# Main_Board.net
KiCad netlist of a schematic drawn in EAGLE
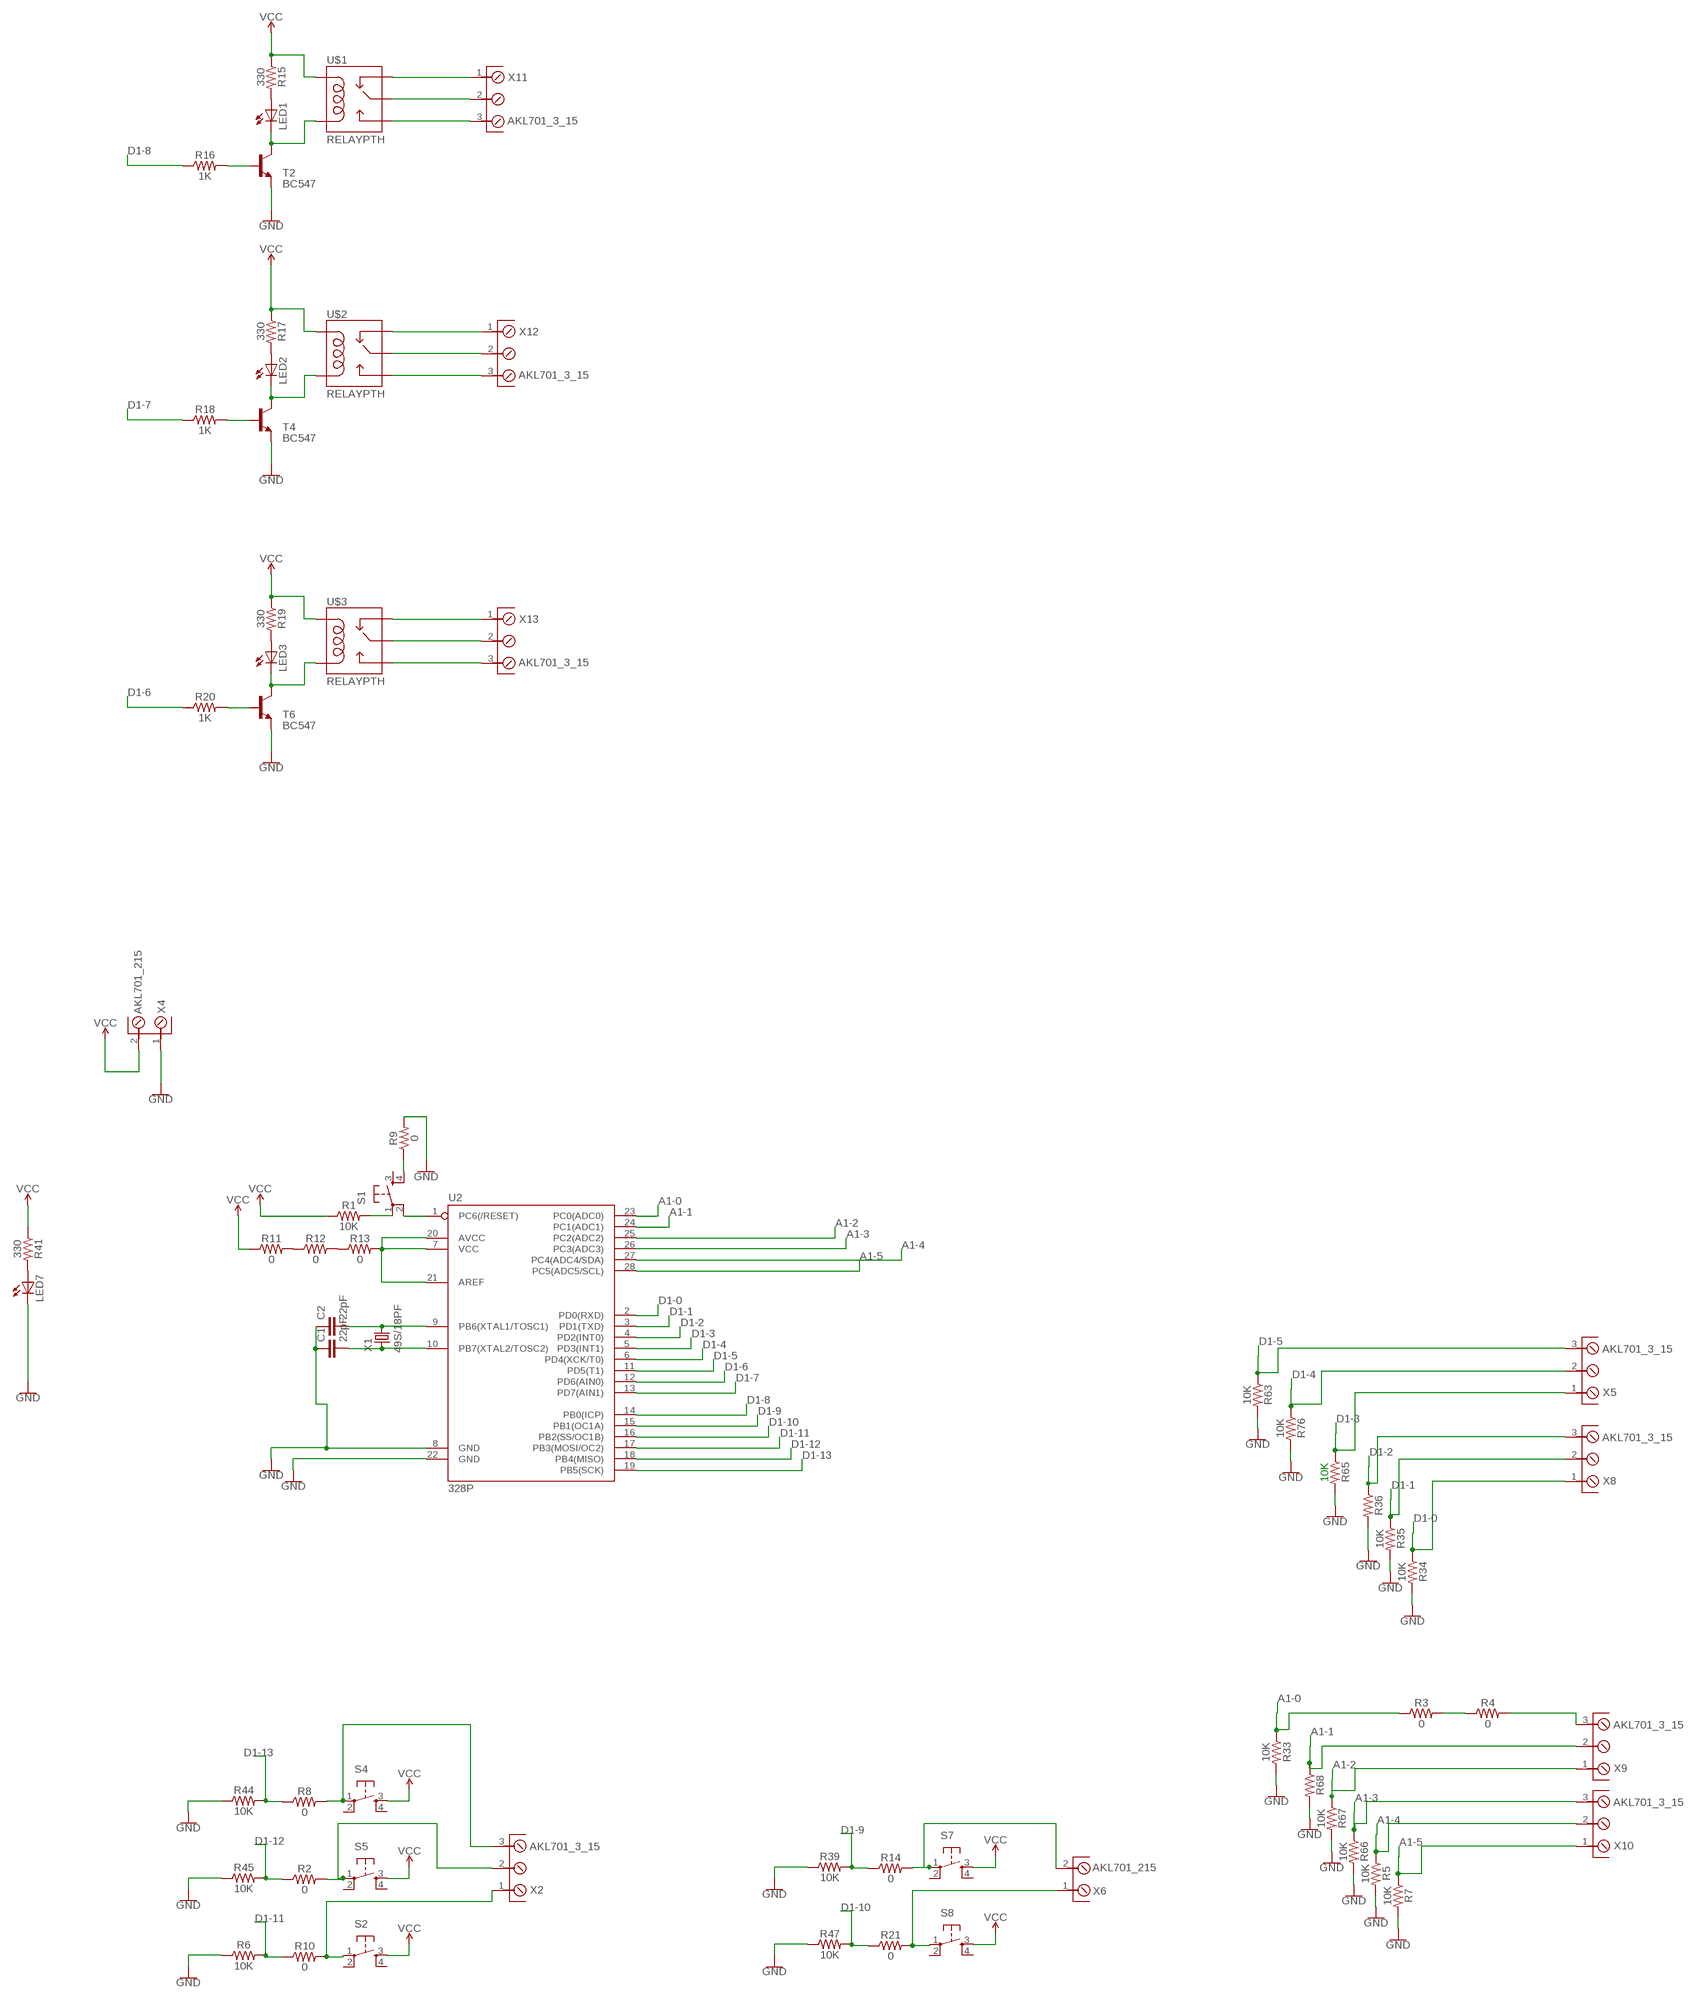
[diagram p0: schematic, sheet 1]

(export (version "E")
  (design (tool "Eeschema 10.0.6"))
  (components
    (comp (ref "C1")
      (value "22pF")
      (footprint "eagle-import:CAP-PTH-2.54")
      (libsource (lib "eagle-import") (part "22PF-PTH-2.54MM-200V-5%"))
    )
    (comp (ref "C2")
      (value "22pF")
      (footprint "eagle-import:CAP-PTH-2.54")
      (libsource (lib "eagle-import") (part "22PF-PTH-2.54MM-200V-5%"))
    )
    (comp (ref "LED1")
      (value "LED5MM")
      (footprint "eagle-import:LED5MM")
      (libsource (lib "eagle-import") (part "LED5MM"))
    )
    (comp (ref "LED2")
      (value "LED5MM")
      (footprint "eagle-import:LED5MM")
      (libsource (lib "eagle-import") (part "LED5MM"))
    )
    (comp (ref "LED3")
      (value "LED5MM")
      (footprint "eagle-import:LED5MM")
      (libsource (lib "eagle-import") (part "LED5MM"))
    )
    (comp (ref "LED7")
      (value "LED5MM")
      (footprint "eagle-import:LED5MM")
      (libsource (lib "eagle-import") (part "LED5MM"))
    )
    (comp (ref "R1")
      (value "10K")
      (footprint "eagle-import:AXIAL-0.3")
      (libsource (lib "eagle-import") (part "10MOHM-HORIZ-1/4W-5%"))
    )
    (comp (ref "R2")
      (value "0")
      (footprint "eagle-import:AXIAL-0.3")
      (libsource (lib "eagle-import") (part "10MOHM-HORIZ-1/4W-5%"))
    )
    (comp (ref "R3")
      (value "0")
      (footprint "eagle-import:AXIAL-0.3")
      (libsource (lib "eagle-import") (part "10MOHM-HORIZ-1/4W-5%"))
    )
    (comp (ref "R4")
      (value "0")
      (footprint "eagle-import:AXIAL-0.3")
      (libsource (lib "eagle-import") (part "10MOHM-HORIZ-1/4W-5%"))
    )
    (comp (ref "R5")
      (value "10K")
      (footprint "eagle-import:AXIAL-0.3")
      (libsource (lib "eagle-import") (part "10MOHM-HORIZ-1/4W-5%"))
    )
    (comp (ref "R6")
      (value "10K")
      (footprint "eagle-import:AXIAL-0.3")
      (libsource (lib "eagle-import") (part "10MOHM-HORIZ-1/4W-5%"))
    )
    (comp (ref "R7")
      (value "10K")
      (footprint "eagle-import:AXIAL-0.3")
      (libsource (lib "eagle-import") (part "10MOHM-HORIZ-1/4W-5%"))
    )
    (comp (ref "R8")
      (value "0")
      (footprint "eagle-import:AXIAL-0.3")
      (libsource (lib "eagle-import") (part "10MOHM-HORIZ-1/4W-5%"))
    )
    (comp (ref "R9")
      (value "0")
      (footprint "eagle-import:AXIAL-0.3")
      (libsource (lib "eagle-import") (part "10MOHM-HORIZ-1/4W-5%"))
    )
    (comp (ref "R10")
      (value "0")
      (footprint "eagle-import:AXIAL-0.3")
      (libsource (lib "eagle-import") (part "10MOHM-HORIZ-1/4W-5%"))
    )
    (comp (ref "R11")
      (value "0")
      (footprint "eagle-import:AXIAL-0.3")
      (libsource (lib "eagle-import") (part "10MOHM-HORIZ-1/4W-5%"))
    )
    (comp (ref "R12")
      (value "0")
      (footprint "eagle-import:AXIAL-0.3")
      (libsource (lib "eagle-import") (part "10MOHM-HORIZ-1/4W-5%"))
    )
    (comp (ref "R13")
      (value "0")
      (footprint "eagle-import:AXIAL-0.3")
      (libsource (lib "eagle-import") (part "10MOHM-HORIZ-1/4W-5%"))
    )
    (comp (ref "R14")
      (value "0")
      (footprint "eagle-import:AXIAL-0.3")
      (libsource (lib "eagle-import") (part "10MOHM-HORIZ-1/4W-5%"))
    )
    (comp (ref "R15")
      (value "330")
      (footprint "eagle-import:AXIAL-0.3")
      (libsource (lib "eagle-import") (part "10MOHM-HORIZ-1/4W-5%"))
    )
    (comp (ref "R16")
      (value "1K")
      (footprint "eagle-import:AXIAL-0.3")
      (libsource (lib "eagle-import") (part "10MOHM-HORIZ-1/4W-5%"))
    )
    (comp (ref "R17")
      (value "330")
      (footprint "eagle-import:AXIAL-0.3")
      (libsource (lib "eagle-import") (part "10MOHM-HORIZ-1/4W-5%"))
    )
    (comp (ref "R18")
      (value "1K")
      (footprint "eagle-import:AXIAL-0.3")
      (libsource (lib "eagle-import") (part "10MOHM-HORIZ-1/4W-5%"))
    )
    (comp (ref "R19")
      (value "330")
      (footprint "eagle-import:AXIAL-0.3")
      (libsource (lib "eagle-import") (part "10MOHM-HORIZ-1/4W-5%"))
    )
    (comp (ref "R20")
      (value "1K")
      (footprint "eagle-import:AXIAL-0.3")
      (libsource (lib "eagle-import") (part "10MOHM-HORIZ-1/4W-5%"))
    )
    (comp (ref "R21")
      (value "0")
      (footprint "eagle-import:AXIAL-0.3")
      (libsource (lib "eagle-import") (part "10MOHM-HORIZ-1/4W-5%"))
    )
    (comp (ref "R33")
      (value "10K")
      (footprint "eagle-import:AXIAL-0.3")
      (libsource (lib "eagle-import") (part "10MOHM-HORIZ-1/4W-5%"))
    )
    (comp (ref "R34")
      (value "10K")
      (footprint "eagle-import:AXIAL-0.3")
      (libsource (lib "eagle-import") (part "10MOHM-HORIZ-1/4W-5%"))
    )
    (comp (ref "R35")
      (value "10K")
      (footprint "eagle-import:AXIAL-0.3")
      (libsource (lib "eagle-import") (part "10MOHM-HORIZ-1/4W-5%"))
    )
    (comp (ref "R36")
      (value "10K")
      (footprint "eagle-import:AXIAL-0.3")
      (libsource (lib "eagle-import") (part "10MOHM-HORIZ-1/4W-5%"))
    )
    (comp (ref "R39")
      (value "10K")
      (footprint "eagle-import:AXIAL-0.3")
      (libsource (lib "eagle-import") (part "10MOHM-HORIZ-1/4W-5%"))
    )
    (comp (ref "R41")
      (value "330")
      (footprint "eagle-import:AXIAL-0.3")
      (libsource (lib "eagle-import") (part "10MOHM-HORIZ-1/4W-5%"))
    )
    (comp (ref "R44")
      (value "10K")
      (footprint "eagle-import:AXIAL-0.3")
      (libsource (lib "eagle-import") (part "10MOHM-HORIZ-1/4W-5%"))
    )
    (comp (ref "R45")
      (value "10K")
      (footprint "eagle-import:AXIAL-0.3")
      (libsource (lib "eagle-import") (part "10MOHM-HORIZ-1/4W-5%"))
    )
    (comp (ref "R47")
      (value "10K")
      (footprint "eagle-import:AXIAL-0.3")
      (libsource (lib "eagle-import") (part "10MOHM-HORIZ-1/4W-5%"))
    )
    (comp (ref "R63")
      (value "10K")
      (footprint "eagle-import:AXIAL-0.3")
      (libsource (lib "eagle-import") (part "10MOHM-HORIZ-1/4W-5%"))
    )
    (comp (ref "R65")
      (value "10K")
      (footprint "eagle-import:AXIAL-0.3")
      (libsource (lib "eagle-import") (part "10MOHM-HORIZ-1/4W-5%"))
    )
    (comp (ref "R66")
      (value "10K")
      (footprint "eagle-import:AXIAL-0.3")
      (libsource (lib "eagle-import") (part "10MOHM-HORIZ-1/4W-5%"))
    )
    (comp (ref "R67")
      (value "10K")
      (footprint "eagle-import:AXIAL-0.3")
      (libsource (lib "eagle-import") (part "10MOHM-HORIZ-1/4W-5%"))
    )
    (comp (ref "R68")
      (value "10K")
      (footprint "eagle-import:AXIAL-0.3")
      (libsource (lib "eagle-import") (part "10MOHM-HORIZ-1/4W-5%"))
    )
    (comp (ref "R76")
      (value "10K")
      (footprint "eagle-import:AXIAL-0.3")
      (libsource (lib "eagle-import") (part "10MOHM-HORIZ-1/4W-5%"))
    )
    (comp (ref "S1")
      (value "TAC_SWITCHPTH")
      (footprint "eagle-import:TACTILE-PTH")
      (libsource (lib "eagle-import") (part "TAC_SWITCHPTH"))
    )
    (comp (ref "S2")
      (value "TAC_SWITCHPTH")
      (footprint "eagle-import:TACTILE-PTH")
      (libsource (lib "eagle-import") (part "TAC_SWITCHPTH"))
    )
    (comp (ref "S4")
      (value "TAC_SWITCHPTH")
      (footprint "eagle-import:TACTILE-PTH")
      (libsource (lib "eagle-import") (part "TAC_SWITCHPTH"))
    )
    (comp (ref "S5")
      (value "TAC_SWITCHPTH")
      (footprint "eagle-import:TACTILE-PTH")
      (libsource (lib "eagle-import") (part "TAC_SWITCHPTH"))
    )
    (comp (ref "S7")
      (value "TAC_SWITCHPTH")
      (footprint "eagle-import:TACTILE-PTH")
      (libsource (lib "eagle-import") (part "TAC_SWITCHPTH"))
    )
    (comp (ref "S8")
      (value "TAC_SWITCHPTH")
      (footprint "eagle-import:TACTILE-PTH")
      (libsource (lib "eagle-import") (part "TAC_SWITCHPTH"))
    )
    (comp (ref "T2")
      (value "BC547")
      (footprint "eagle-import:TO92")
      (libsource (lib "eagle-import") (part "BC547"))
    )
    (comp (ref "T4")
      (value "BC547")
      (footprint "eagle-import:TO92")
      (libsource (lib "eagle-import") (part "BC547"))
    )
    (comp (ref "T6")
      (value "BC547")
      (footprint "eagle-import:TO92")
      (libsource (lib "eagle-import") (part "BC547"))
    )
    (comp (ref "U$1")
      (value "RELAYPTH")
      (footprint "eagle-import:SRD-05VDC-SL-C")
      (libsource (lib "eagle-import") (part "RELAYPTH"))
    )
    (comp (ref "U$2")
      (value "RELAYPTH")
      (footprint "eagle-import:SRD-05VDC-SL-C")
      (libsource (lib "eagle-import") (part "RELAYPTH"))
    )
    (comp (ref "U$3")
      (value "RELAYPTH")
      (footprint "eagle-import:SRD-05VDC-SL-C")
      (libsource (lib "eagle-import") (part "RELAYPTH"))
    )
    (comp (ref "U2")
      (value "328P")
      (footprint "eagle-import:DIP28")
      (libsource (lib "eagle-import") (part "ATMEGA328P_PDIP"))
    )
    (comp (ref "X1")
      (value "49S/18PF")
      (footprint "eagle-import:XTAL_HC49")
      (fields (field (name "MANUFACTURER") "Xinhunjing ") (field (name "CREATED_BY") "PCBLayout.com"))
      (libsource (lib "eagle-import") (part "49S/18PF"))
    )
    (comp (ref "X2")
      (value "AKL701_3_15")
      (footprint "eagle-import:AKL701_3_15")
      (libsource (lib "eagle-import") (part "AKL701_3_15"))
    )
    (comp (ref "X4")
      (value "AKL701_215")
      (footprint "eagle-import:AKL701_2_15")
      (libsource (lib "eagle-import") (part "AKL701_215"))
    )
    (comp (ref "X5")
      (value "AKL701_3_15")
      (footprint "eagle-import:AKL701_3_15")
      (libsource (lib "eagle-import") (part "AKL701_3_15"))
    )
    (comp (ref "X6")
      (value "AKL701_215")
      (footprint "eagle-import:AKL701_2_15")
      (libsource (lib "eagle-import") (part "AKL701_215"))
    )
    (comp (ref "X8")
      (value "AKL701_3_15")
      (footprint "eagle-import:AKL701_3_15")
      (libsource (lib "eagle-import") (part "AKL701_3_15"))
    )
    (comp (ref "X9")
      (value "AKL701_3_15")
      (footprint "eagle-import:AKL701_3_15")
      (libsource (lib "eagle-import") (part "AKL701_3_15"))
    )
    (comp (ref "X10")
      (value "AKL701_3_15")
      (footprint "eagle-import:AKL701_3_15")
      (libsource (lib "eagle-import") (part "AKL701_3_15"))
    )
    (comp (ref "X11")
      (value "AKL701_3_15")
      (footprint "eagle-import:AKL701_3_15")
      (libsource (lib "eagle-import") (part "AKL701_3_15"))
    )
    (comp (ref "X12")
      (value "AKL701_3_15")
      (footprint "eagle-import:AKL701_3_15")
      (libsource (lib "eagle-import") (part "AKL701_3_15"))
    )
    (comp (ref "X13")
      (value "AKL701_3_15")
      (footprint "eagle-import:AKL701_3_15")
      (libsource (lib "eagle-import") (part "AKL701_3_15"))
    )
  )
  (nets
    (net (code "1") (name "/A1-0") (class "Default")
      (node (ref "R3") (pin "P$1") (pinfunction "1_P$1") (pintype "passive"))
      (node (ref "R33") (pin "P$1") (pinfunction "1_P$1") (pintype "passive"))
      (node (ref "U2") (pin "23") (pinfunction "PC0(ADC0)_23") (pintype "bidirectional"))
    )
    (net (code "2") (name "/A1-1") (class "Default")
      (node (ref "R68") (pin "P$1") (pinfunction "1_P$1") (pintype "passive"))
      (node (ref "U2") (pin "24") (pinfunction "PC1(ADC1)_24") (pintype "bidirectional"))
      (node (ref "X9") (pin "2") (pinfunction "2_2") (pintype "passive"))
    )
    (net (code "3") (name "/A1-2") (class "Default")
      (node (ref "R67") (pin "P$1") (pinfunction "1_P$1") (pintype "passive"))
      (node (ref "U2") (pin "25") (pinfunction "PC2(ADC2)_25") (pintype "bidirectional"))
      (node (ref "X9") (pin "1") (pinfunction "1_1") (pintype "passive"))
    )
    (net (code "4") (name "/A1-3") (class "Default")
      (node (ref "R66") (pin "P$1") (pinfunction "1_P$1") (pintype "passive"))
      (node (ref "U2") (pin "26") (pinfunction "PC3(ADC3)_26") (pintype "bidirectional"))
      (node (ref "X10") (pin "3") (pinfunction "3_3") (pintype "passive"))
    )
    (net (code "5") (name "/A1-4") (class "Default")
      (node (ref "R5") (pin "P$1") (pinfunction "1_P$1") (pintype "passive"))
      (node (ref "U2") (pin "27") (pinfunction "PC4(ADC4/SDA)_27") (pintype "bidirectional"))
      (node (ref "X10") (pin "2") (pinfunction "2_2") (pintype "passive"))
    )
    (net (code "6") (name "/A1-5") (class "Default")
      (node (ref "R7") (pin "P$1") (pinfunction "1_P$1") (pintype "passive"))
      (node (ref "U2") (pin "28") (pinfunction "PC5(ADC5/SCL)_28") (pintype "bidirectional"))
      (node (ref "X10") (pin "1") (pinfunction "1_1") (pintype "passive"))
    )
    (net (code "7") (name "/D1-0") (class "Default")
      (node (ref "R34") (pin "P$1") (pinfunction "1_P$1") (pintype "passive"))
      (node (ref "U2") (pin "2") (pinfunction "PD0(RXD)_2") (pintype "bidirectional"))
      (node (ref "X8") (pin "1") (pinfunction "1_1") (pintype "passive"))
    )
    (net (code "8") (name "/D1-1") (class "Default")
      (node (ref "R35") (pin "P$1") (pinfunction "1_P$1") (pintype "passive"))
      (node (ref "U2") (pin "3") (pinfunction "PD1(TXD)_3") (pintype "bidirectional"))
      (node (ref "X8") (pin "2") (pinfunction "2_2") (pintype "passive"))
    )
    (net (code "9") (name "/D1-2") (class "Default")
      (node (ref "R36") (pin "P$1") (pinfunction "1_P$1") (pintype "passive"))
      (node (ref "U2") (pin "4") (pinfunction "PD2(INT0)_4") (pintype "bidirectional"))
      (node (ref "X8") (pin "3") (pinfunction "3_3") (pintype "passive"))
    )
    (net (code "10") (name "/D1-3") (class "Default")
      (node (ref "R65") (pin "P$1") (pinfunction "1_P$1") (pintype "passive"))
      (node (ref "U2") (pin "5") (pinfunction "PD3(INT1)_5") (pintype "bidirectional"))
      (node (ref "X5") (pin "1") (pinfunction "1_1") (pintype "passive"))
    )
    (net (code "11") (name "/D1-4") (class "Default")
      (node (ref "R76") (pin "P$1") (pinfunction "1_P$1") (pintype "passive"))
      (node (ref "U2") (pin "6") (pinfunction "PD4(XCK/T0)_6") (pintype "bidirectional"))
      (node (ref "X5") (pin "2") (pinfunction "2_2") (pintype "passive"))
    )
    (net (code "12") (name "/D1-5") (class "Default")
      (node (ref "R63") (pin "P$1") (pinfunction "1_P$1") (pintype "passive"))
      (node (ref "U2") (pin "11") (pinfunction "PD5(T1)_11") (pintype "bidirectional"))
      (node (ref "X5") (pin "3") (pinfunction "3_3") (pintype "passive"))
    )
    (net (code "13") (name "/D1-6") (class "Default")
      (node (ref "R20") (pin "P$1") (pinfunction "1_P$1") (pintype "passive"))
      (node (ref "U2") (pin "12") (pinfunction "PD6(AIN0)_12") (pintype "bidirectional"))
    )
    (net (code "14") (name "/D1-7") (class "Default")
      (node (ref "R18") (pin "P$1") (pinfunction "1_P$1") (pintype "passive"))
      (node (ref "U2") (pin "13") (pinfunction "PD7(AIN1)_13") (pintype "bidirectional"))
    )
    (net (code "15") (name "/D1-8") (class "Default")
      (node (ref "R16") (pin "P$1") (pinfunction "1_P$1") (pintype "passive"))
      (node (ref "U2") (pin "14") (pinfunction "PB0(ICP)_14") (pintype "bidirectional"))
    )
    (net (code "16") (name "/D1-9") (class "Default")
      (node (ref "R14") (pin "P$1") (pinfunction "1_P$1") (pintype "passive"))
      (node (ref "R39") (pin "P$2") (pinfunction "2_P$2") (pintype "passive"))
      (node (ref "U2") (pin "15") (pinfunction "PB1(OC1A)_15") (pintype "bidirectional"))
    )
    (net (code "17") (name "/D1-10") (class "Default")
      (node (ref "R21") (pin "P$1") (pinfunction "1_P$1") (pintype "passive"))
      (node (ref "R47") (pin "P$2") (pinfunction "2_P$2") (pintype "passive"))
      (node (ref "U2") (pin "16") (pinfunction "PB2(SS/OC1B)_16") (pintype "bidirectional"))
    )
    (net (code "18") (name "/D1-11") (class "Default")
      (node (ref "R10") (pin "P$1") (pinfunction "1_P$1") (pintype "passive"))
      (node (ref "R6") (pin "P$2") (pinfunction "2_P$2") (pintype "passive"))
      (node (ref "U2") (pin "17") (pinfunction "PB3(MOSI/OC2)_17") (pintype "bidirectional"))
    )
    (net (code "19") (name "/D1-12") (class "Default")
      (node (ref "R2") (pin "P$1") (pinfunction "1_P$1") (pintype "passive"))
      (node (ref "R45") (pin "P$2") (pinfunction "2_P$2") (pintype "passive"))
      (node (ref "U2") (pin "18") (pinfunction "PB4(MISO)_18") (pintype "bidirectional"))
    )
    (net (code "20") (name "/D1-13") (class "Default")
      (node (ref "R44") (pin "P$2") (pinfunction "2_P$2") (pintype "passive"))
      (node (ref "R8") (pin "P$1") (pinfunction "1_P$1") (pintype "passive"))
      (node (ref "U2") (pin "19") (pinfunction "PB5(SCK)_19") (pintype "bidirectional"))
    )
    (net (code "21") (name "GND") (class "Default")
      (node (ref "C1") (pin "1") (pinfunction "1_1") (pintype "passive"))
      (node (ref "C2") (pin "1") (pinfunction "1_1") (pintype "passive"))
      (node (ref "LED7") (pin "K") (pinfunction "C_K") (pintype "passive"))
      (node (ref "R33") (pin "P$2") (pinfunction "2_P$2") (pintype "passive"))
      (node (ref "R34") (pin "P$2") (pinfunction "2_P$2") (pintype "passive"))
      (node (ref "R35") (pin "P$2") (pinfunction "2_P$2") (pintype "passive"))
      (node (ref "R36") (pin "P$2") (pinfunction "2_P$2") (pintype "passive"))
      (node (ref "R39") (pin "P$1") (pinfunction "1_P$1") (pintype "passive"))
      (node (ref "R44") (pin "P$1") (pinfunction "1_P$1") (pintype "passive"))
      (node (ref "R45") (pin "P$1") (pinfunction "1_P$1") (pintype "passive"))
      (node (ref "R47") (pin "P$1") (pinfunction "1_P$1") (pintype "passive"))
      (node (ref "R5") (pin "P$2") (pinfunction "2_P$2") (pintype "passive"))
      (node (ref "R6") (pin "P$1") (pinfunction "1_P$1") (pintype "passive"))
      (node (ref "R63") (pin "P$2") (pinfunction "2_P$2") (pintype "passive"))
      (node (ref "R65") (pin "P$2") (pinfunction "2_P$2") (pintype "passive"))
      (node (ref "R66") (pin "P$2") (pinfunction "2_P$2") (pintype "passive"))
      (node (ref "R67") (pin "P$2") (pinfunction "2_P$2") (pintype "passive"))
      (node (ref "R68") (pin "P$2") (pinfunction "2_P$2") (pintype "passive"))
      (node (ref "R7") (pin "P$2") (pinfunction "2_P$2") (pintype "passive"))
      (node (ref "R76") (pin "P$2") (pinfunction "2_P$2") (pintype "passive"))
      (node (ref "R9") (pin "P$2") (pinfunction "2_P$2") (pintype "passive"))
      (node (ref "T2") (pin "1") (pinfunction "E_1") (pintype "passive"))
      (node (ref "T4") (pin "1") (pinfunction "E_1") (pintype "passive"))
      (node (ref "T6") (pin "1") (pinfunction "E_1") (pintype "passive"))
      (node (ref "U2") (pin "22") (pinfunction "GND_22") (pintype "bidirectional"))
      (node (ref "U2") (pin "8") (pinfunction "GND_8") (pintype "bidirectional"))
      (node (ref "X4") (pin "1") (pinfunction "1_1") (pintype "passive"))
    )
    (net (code "22") (name "Net-(LED1-C)") (class "Default")
      (node (ref "LED1") (pin "K") (pinfunction "C_K") (pintype "passive"))
      (node (ref "T2") (pin "3") (pinfunction "C_3") (pintype "passive"))
      (node (ref "U$1") (pin "COIL0") (pinfunction "COIL0_COIL0") (pintype "bidirectional"))
    )
    (net (code "23") (name "Net-(LED2-C)") (class "Default")
      (node (ref "LED2") (pin "K") (pinfunction "C_K") (pintype "passive"))
      (node (ref "T4") (pin "3") (pinfunction "C_3") (pintype "passive"))
      (node (ref "U$2") (pin "COIL0") (pinfunction "COIL0_COIL0") (pintype "bidirectional"))
    )
    (net (code "24") (name "Net-(LED3-C)") (class "Default")
      (node (ref "LED3") (pin "K") (pinfunction "C_K") (pintype "passive"))
      (node (ref "T6") (pin "3") (pinfunction "C_3") (pintype "passive"))
      (node (ref "U$3") (pin "COIL0") (pinfunction "COIL0_COIL0") (pintype "bidirectional"))
    )
    (net (code "25") (name "Net-(R1-2)") (class "Default")
      (node (ref "R1") (pin "P$2") (pinfunction "2_P$2") (pintype "passive"))
      (node (ref "S1") (pin "1") (pinfunction "1_1") (pintype "passive"))
    )
    (net (code "26") (name "Net-(R2-2)") (class "Default")
      (node (ref "R2") (pin "P$2") (pinfunction "2_P$2") (pintype "passive"))
      (node (ref "S5") (pin "1") (pinfunction "1_1") (pintype "passive"))
      (node (ref "X2") (pin "2") (pinfunction "2_2") (pintype "passive"))
    )
    (net (code "27") (name "Net-(R3-2)") (class "Default")
      (node (ref "R3") (pin "P$2") (pinfunction "2_P$2") (pintype "passive"))
      (node (ref "R4") (pin "P$1") (pinfunction "1_P$1") (pintype "passive"))
    )
    (net (code "28") (name "Net-(R4-2)") (class "Default")
      (node (ref "R4") (pin "P$2") (pinfunction "2_P$2") (pintype "passive"))
      (node (ref "X9") (pin "3") (pinfunction "3_3") (pintype "passive"))
    )
    (net (code "29") (name "Net-(R8-2)") (class "Default")
      (node (ref "R8") (pin "P$2") (pinfunction "2_P$2") (pintype "passive"))
      (node (ref "S4") (pin "1") (pinfunction "1_1") (pintype "passive"))
      (node (ref "X2") (pin "3") (pinfunction "3_3") (pintype "passive"))
    )
    (net (code "30") (name "Net-(R9-1)") (class "Default")
      (node (ref "R9") (pin "P$1") (pinfunction "1_P$1") (pintype "passive"))
      (node (ref "S1") (pin "4") (pinfunction "4_4") (pintype "passive"))
    )
    (net (code "31") (name "Net-(R10-2)") (class "Default")
      (node (ref "R10") (pin "P$2") (pinfunction "2_P$2") (pintype "passive"))
      (node (ref "S2") (pin "1") (pinfunction "1_1") (pintype "passive"))
      (node (ref "X2") (pin "1") (pinfunction "1_1") (pintype "passive"))
    )
    (net (code "32") (name "Net-(R11-2)") (class "Default")
      (node (ref "R11") (pin "P$2") (pinfunction "2_P$2") (pintype "passive"))
      (node (ref "R12") (pin "P$1") (pinfunction "1_P$1") (pintype "passive"))
    )
    (net (code "33") (name "Net-(R12-2)") (class "Default")
      (node (ref "R12") (pin "P$2") (pinfunction "2_P$2") (pintype "passive"))
      (node (ref "R13") (pin "P$1") (pinfunction "1_P$1") (pintype "passive"))
    )
    (net (code "34") (name "Net-(R13-2)") (class "Default")
      (node (ref "R13") (pin "P$2") (pinfunction "2_P$2") (pintype "passive"))
      (node (ref "U2") (pin "20") (pinfunction "AVCC_20") (pintype "bidirectional"))
      (node (ref "U2") (pin "21") (pinfunction "AREF_21") (pintype "bidirectional"))
      (node (ref "U2") (pin "7") (pinfunction "VCC_7") (pintype "bidirectional"))
    )
    (net (code "35") (name "Net-(R14-2)") (class "Default")
      (node (ref "R14") (pin "P$2") (pinfunction "2_P$2") (pintype "passive"))
      (node (ref "S7") (pin "1") (pinfunction "1_1") (pintype "passive"))
      (node (ref "X6") (pin "2") (pinfunction "2_2") (pintype "passive"))
    )
    (net (code "36") (name "Net-(R15-2)") (class "Default")
      (node (ref "LED1") (pin "A") (pinfunction "A_A") (pintype "passive"))
      (node (ref "R15") (pin "P$2") (pinfunction "2_P$2") (pintype "passive"))
    )
    (net (code "37") (name "Net-(R16-2)") (class "Default")
      (node (ref "R16") (pin "P$2") (pinfunction "2_P$2") (pintype "passive"))
      (node (ref "T2") (pin "2") (pinfunction "B_2") (pintype "passive"))
    )
    (net (code "38") (name "Net-(R17-2)") (class "Default")
      (node (ref "LED2") (pin "A") (pinfunction "A_A") (pintype "passive"))
      (node (ref "R17") (pin "P$2") (pinfunction "2_P$2") (pintype "passive"))
    )
    (net (code "39") (name "Net-(R18-2)") (class "Default")
      (node (ref "R18") (pin "P$2") (pinfunction "2_P$2") (pintype "passive"))
      (node (ref "T4") (pin "2") (pinfunction "B_2") (pintype "passive"))
    )
    (net (code "40") (name "Net-(R19-2)") (class "Default")
      (node (ref "LED3") (pin "A") (pinfunction "A_A") (pintype "passive"))
      (node (ref "R19") (pin "P$2") (pinfunction "2_P$2") (pintype "passive"))
    )
    (net (code "41") (name "Net-(R20-2)") (class "Default")
      (node (ref "R20") (pin "P$2") (pinfunction "2_P$2") (pintype "passive"))
      (node (ref "T6") (pin "2") (pinfunction "B_2") (pintype "passive"))
    )
    (net (code "42") (name "Net-(R21-2)") (class "Default")
      (node (ref "R21") (pin "P$2") (pinfunction "2_P$2") (pintype "passive"))
      (node (ref "S8") (pin "1") (pinfunction "1_1") (pintype "passive"))
      (node (ref "X6") (pin "1") (pinfunction "1_1") (pintype "passive"))
    )
    (net (code "43") (name "Net-(R41-2)") (class "Default")
      (node (ref "LED7") (pin "A") (pinfunction "A_A") (pintype "passive"))
      (node (ref "R41") (pin "P$2") (pinfunction "2_P$2") (pintype "passive"))
    )
    (net (code "44") (name "Net-(U$1-PadSWCOMMON)") (class "Default")
      (node (ref "U$1") (pin "SWCOMMON") (pinfunction "SWCOMMON_SWCOMMON") (pintype "bidirectional"))
      (node (ref "X11") (pin "2") (pinfunction "2_2") (pintype "passive"))
    )
    (net (code "45") (name "Net-(U$1-PadSWOPEN)") (class "Default")
      (node (ref "U$1") (pin "SWOPEN") (pinfunction "SWOPEN_SWOPEN") (pintype "bidirectional"))
      (node (ref "X11") (pin "3") (pinfunction "3_3") (pintype "passive"))
    )
    (net (code "46") (name "Net-(U$1-SWCLOSE)") (class "Default")
      (node (ref "U$1") (pin "SWCLOSED") (pinfunction "SWCLOSE_SWCLOSED") (pintype "bidirectional"))
      (node (ref "X11") (pin "1") (pinfunction "1_1") (pintype "passive"))
    )
    (net (code "47") (name "Net-(U$2-PadSWCOMMON)") (class "Default")
      (node (ref "U$2") (pin "SWCOMMON") (pinfunction "SWCOMMON_SWCOMMON") (pintype "bidirectional"))
      (node (ref "X12") (pin "2") (pinfunction "2_2") (pintype "passive"))
    )
    (net (code "48") (name "Net-(U$2-PadSWOPEN)") (class "Default")
      (node (ref "U$2") (pin "SWOPEN") (pinfunction "SWOPEN_SWOPEN") (pintype "bidirectional"))
      (node (ref "X12") (pin "3") (pinfunction "3_3") (pintype "passive"))
    )
    (net (code "49") (name "Net-(U$2-SWCLOSE)") (class "Default")
      (node (ref "U$2") (pin "SWCLOSED") (pinfunction "SWCLOSE_SWCLOSED") (pintype "bidirectional"))
      (node (ref "X12") (pin "1") (pinfunction "1_1") (pintype "passive"))
    )
    (net (code "50") (name "Net-(U$3-PadSWCOMMON)") (class "Default")
      (node (ref "U$3") (pin "SWCOMMON") (pinfunction "SWCOMMON_SWCOMMON") (pintype "bidirectional"))
      (node (ref "X13") (pin "2") (pinfunction "2_2") (pintype "passive"))
    )
    (net (code "51") (name "Net-(U$3-PadSWOPEN)") (class "Default")
      (node (ref "U$3") (pin "SWOPEN") (pinfunction "SWOPEN_SWOPEN") (pintype "bidirectional"))
      (node (ref "X13") (pin "3") (pinfunction "3_3") (pintype "passive"))
    )
    (net (code "52") (name "Net-(U$3-SWCLOSE)") (class "Default")
      (node (ref "U$3") (pin "SWCLOSED") (pinfunction "SWCLOSE_SWCLOSED") (pintype "bidirectional"))
      (node (ref "X13") (pin "1") (pinfunction "1_1") (pintype "passive"))
    )
    (net (code "53") (name "Net-(U2-PB6(XTAL1{slash}TOSC1))") (class "Default")
      (node (ref "C2") (pin "2") (pinfunction "2_2") (pintype "passive"))
      (node (ref "U2") (pin "9") (pinfunction "PB6(XTAL1/TOSC1)_9") (pintype "bidirectional"))
      (node (ref "X1") (pin "2") (pinfunction "2_2") (pintype "passive"))
    )
    (net (code "54") (name "Net-(U2-PB7(XTAL2{slash}TOSC2))") (class "Default")
      (node (ref "C1") (pin "2") (pinfunction "2_2") (pintype "passive"))
      (node (ref "U2") (pin "10") (pinfunction "PB7(XTAL2/TOSC2)_10") (pintype "bidirectional"))
      (node (ref "X1") (pin "1") (pinfunction "1_1") (pintype "passive"))
    )
    (net (code "55") (name "Net-(U2-PC6({slash}RESET))") (class "Default")
      (node (ref "S1") (pin "2") (pinfunction "2_2") (pintype "passive"))
      (node (ref "U2") (pin "1") (pinfunction "PC6(/RESET)_1") (pintype "bidirectional"))
    )
    (net (code "56") (name "VCC") (class "Default")
      (node (ref "R1") (pin "P$1") (pinfunction "1_P$1") (pintype "passive"))
      (node (ref "R11") (pin "P$1") (pinfunction "1_P$1") (pintype "passive"))
      (node (ref "R15") (pin "P$1") (pinfunction "1_P$1") (pintype "passive"))
      (node (ref "R17") (pin "P$1") (pinfunction "1_P$1") (pintype "passive"))
      (node (ref "R19") (pin "P$1") (pinfunction "1_P$1") (pintype "passive"))
      (node (ref "R41") (pin "P$1") (pinfunction "1_P$1") (pintype "passive"))
      (node (ref "S2") (pin "3") (pinfunction "3_3") (pintype "passive"))
      (node (ref "S4") (pin "3") (pinfunction "3_3") (pintype "passive"))
      (node (ref "S5") (pin "3") (pinfunction "3_3") (pintype "passive"))
      (node (ref "S7") (pin "3") (pinfunction "3_3") (pintype "passive"))
      (node (ref "S8") (pin "3") (pinfunction "3_3") (pintype "passive"))
      (node (ref "U$1") (pin "COIL1") (pinfunction "COIL1_COIL1") (pintype "bidirectional"))
      (node (ref "U$2") (pin "COIL1") (pinfunction "COIL1_COIL1") (pintype "bidirectional"))
      (node (ref "U$3") (pin "COIL1") (pinfunction "COIL1_COIL1") (pintype "bidirectional"))
      (node (ref "X4") (pin "2") (pinfunction "2_2") (pintype "passive"))
    )
    (net (code "57") (name "unconnected-(S1-Pad3)") (class "Default")
      (node (ref "S1") (pin "3") (pinfunction "3_3") (pintype "passive"))
    )
    (net (code "58") (name "unconnected-(S2-Pad2)") (class "Default")
      (node (ref "S2") (pin "2") (pinfunction "2_2") (pintype "passive"))
    )
    (net (code "59") (name "unconnected-(S2-Pad4)") (class "Default")
      (node (ref "S2") (pin "4") (pinfunction "4_4") (pintype "passive"))
    )
    (net (code "60") (name "unconnected-(S4-Pad2)") (class "Default")
      (node (ref "S4") (pin "2") (pinfunction "2_2") (pintype "passive"))
    )
    (net (code "61") (name "unconnected-(S4-Pad4)") (class "Default")
      (node (ref "S4") (pin "4") (pinfunction "4_4") (pintype "passive"))
    )
    (net (code "62") (name "unconnected-(S5-Pad2)") (class "Default")
      (node (ref "S5") (pin "2") (pinfunction "2_2") (pintype "passive"))
    )
    (net (code "63") (name "unconnected-(S5-Pad4)") (class "Default")
      (node (ref "S5") (pin "4") (pinfunction "4_4") (pintype "passive"))
    )
    (net (code "64") (name "unconnected-(S7-Pad2)") (class "Default")
      (node (ref "S7") (pin "2") (pinfunction "2_2") (pintype "passive"))
    )
    (net (code "65") (name "unconnected-(S7-Pad4)") (class "Default")
      (node (ref "S7") (pin "4") (pinfunction "4_4") (pintype "passive"))
    )
    (net (code "66") (name "unconnected-(S8-Pad2)") (class "Default")
      (node (ref "S8") (pin "2") (pinfunction "2_2") (pintype "passive"))
    )
    (net (code "67") (name "unconnected-(S8-Pad4)") (class "Default")
      (node (ref "S8") (pin "4") (pinfunction "4_4") (pintype "passive"))
    )
  )
)
